# Puente_H.net
KiCad netlist of a schematic drawn in Altium Designer
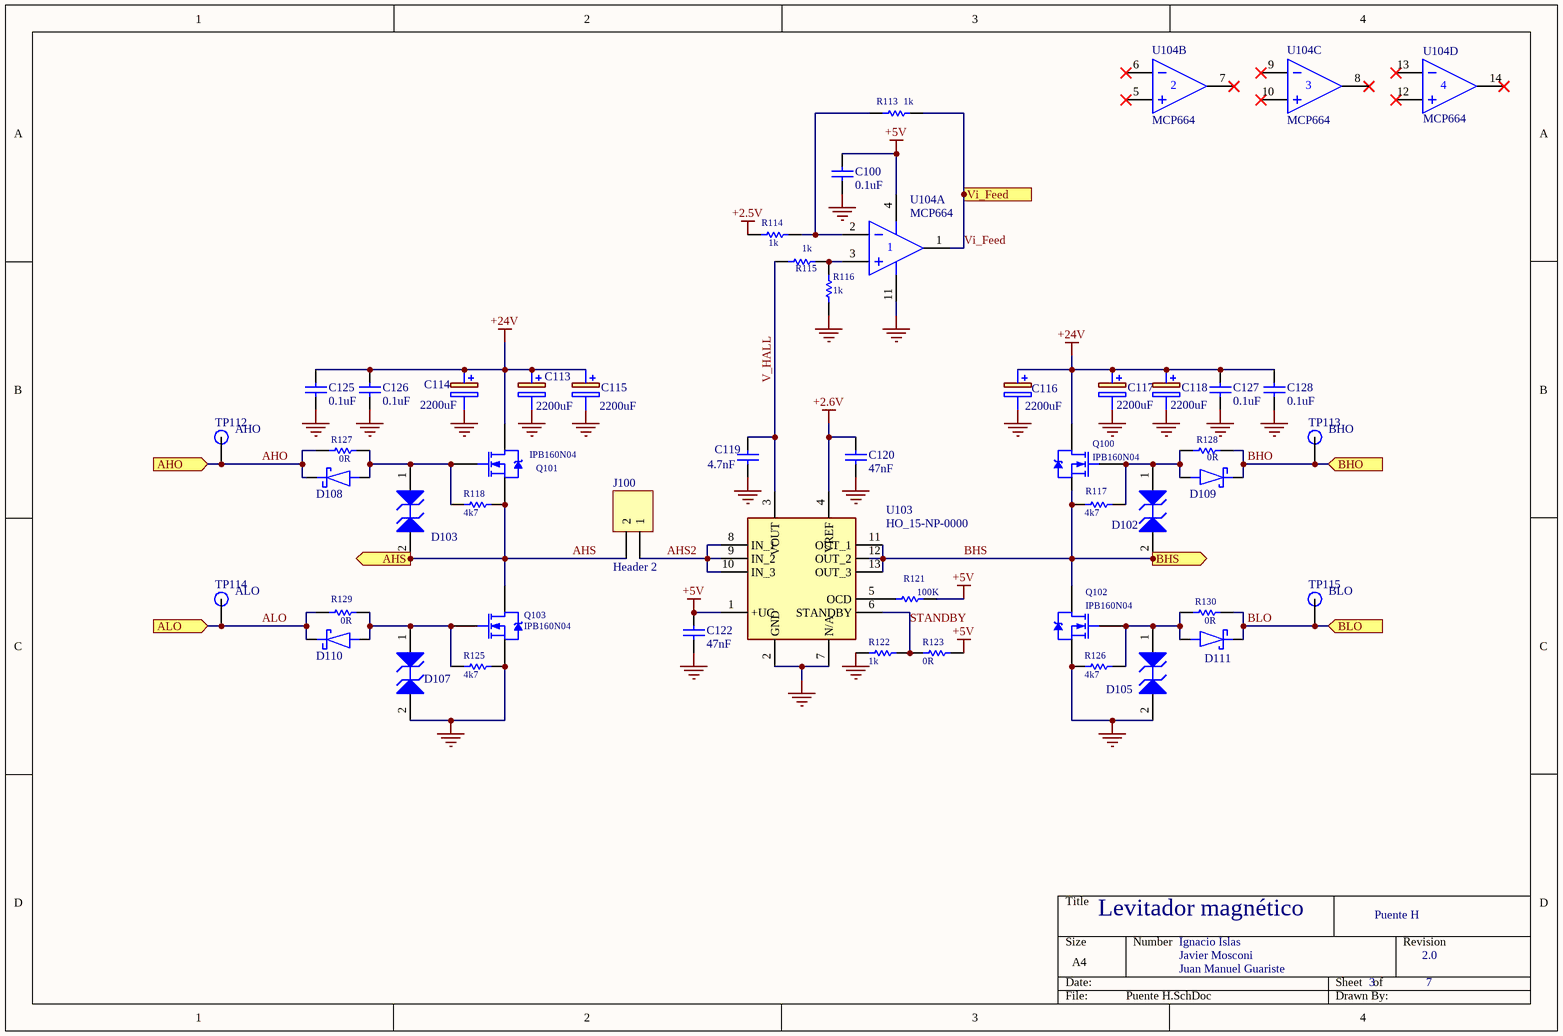
[diagram p0: Puente H.SchDoc]

(export (version "E")
  (design (tool "Eeschema 10.0.6"))
  (components
    (comp (ref "C100")
      (value "0.1uF")
      (footprint "C1206")
      (description "CAP CER 0.1UF 50V X7R 1206")
      (fields (field (name "MANUFACTURER") "Venkel") (field (name "Comment") "Capacitor"))
      (libsource (lib "Levitador_GMI") (part "Capacitor"))
    )
    (comp (ref "C113")
      (value "2200uF")
      (footprint "CAPPRD500W60D1300H2650")
      (description "CAP ALUM 2200UF 20% 35V RADIAL")
      (fields (field (name "MANUFACTURER") "United Chemi-Con") (field (name "Comment") "EKY-350ELL102MK25S"))
      (libsource (lib "Levitador_GMI") (part "EKY-350ELL102MK25S"))
    )
    (comp (ref "C114")
      (value "2200uF")
      (footprint "CAPPRD500W60D1300H2650")
      (description "CAP ALUM 2200UF 20% 35V RADIAL")
      (fields (field (name "MANUFACTURER") "United Chemi-Con") (field (name "Comment") "EKY-350ELL102MK25S"))
      (libsource (lib "Levitador_GMI") (part "EKY-350ELL102MK25S"))
    )
    (comp (ref "C115")
      (value "2200uF")
      (footprint "CAPPRD500W60D1300H2650")
      (description "CAP ALUM 2200UF 20% 35V RADIAL")
      (fields (field (name "MANUFACTURER") "United Chemi-Con") (field (name "Comment") "EKY-350ELL102MK25S"))
      (libsource (lib "Levitador_GMI") (part "EKY-350ELL102MK25S"))
    )
    (comp (ref "C116")
      (value "2200uF")
      (footprint "CAPPRD500W60D1300H2650")
      (description "CAP ALUM 2200UF 20% 35V RADIAL")
      (fields (field (name "MANUFACTURER") "United Chemi-Con") (field (name "Comment") "EKY-350ELL102MK25S"))
      (libsource (lib "Levitador_GMI") (part "EKY-350ELL102MK25S"))
    )
    (comp (ref "C117")
      (value "2200uF")
      (footprint "CAPPRD500W60D1300H2650")
      (description "CAP ALUM 2200UF 20% 35V RADIAL")
      (fields (field (name "MANUFACTURER") "United Chemi-Con") (field (name "Comment") "EKY-350ELL102MK25S"))
      (libsource (lib "Levitador_GMI") (part "EKY-350ELL102MK25S"))
    )
    (comp (ref "C118")
      (value "2200uF")
      (footprint "CAPPRD500W60D1300H2650")
      (description "CAP ALUM 2200UF 20% 35V RADIAL")
      (fields (field (name "MANUFACTURER") "United Chemi-Con") (field (name "Comment") "EKY-350ELL102MK25S"))
      (libsource (lib "Levitador_GMI") (part "EKY-350ELL102MK25S"))
    )
    (comp (ref "C119")
      (value "4.7nF")
      (footprint "C1206")
      (description "CAP CER 4700PF 200V X7R 1206")
      (fields (field (name "MANUFACTURER") "CAL-CHIP ELECTRONICS, INC.") (field (name "Comment") "Capacitor"))
      (libsource (lib "Levitador_GMI") (part "Capacitor"))
    )
    (comp (ref "C120")
      (value "47nF")
      (footprint "C1206")
      (description "CAP CER 0.047UF 50V C0G/NP0 1206")
      (fields (field (name "MANUFACTURER") "CAL-CHIP ELECTRONICS, INC.") (field (name "Comment") "Capacitor"))
      (libsource (lib "Levitador_GMI") (part "Capacitor"))
    )
    (comp (ref "C122")
      (value "47nF")
      (footprint "C1206")
      (description "CAP CER 0.047UF 50V C0G/NP0 1206")
      (fields (field (name "MANUFACTURER") "CAL-CHIP ELECTRONICS, INC.") (field (name "Comment") "Capacitor"))
      (libsource (lib "Levitador_GMI") (part "Capacitor"))
    )
    (comp (ref "C125")
      (value "0.1uF")
      (footprint "C1206")
      (description "CAP CER 0.1UF 50V X7R 1206")
      (fields (field (name "MANUFACTURER") "Venkel") (field (name "Comment") "Capacitor"))
      (libsource (lib "Levitador_GMI") (part "Capacitor"))
    )
    (comp (ref "C126")
      (value "0.1uF")
      (footprint "C1206")
      (description "CAP CER 0.1UF 50V X7R 1206")
      (fields (field (name "MANUFACTURER") "Venkel") (field (name "Comment") "Capacitor"))
      (libsource (lib "Levitador_GMI") (part "Capacitor"))
    )
    (comp (ref "C127")
      (value "0.1uF")
      (footprint "C1206")
      (description "CAP CER 0.1UF 50V X7R 1206")
      (fields (field (name "MANUFACTURER") "Venkel") (field (name "Comment") "Capacitor"))
      (libsource (lib "Levitador_GMI") (part "Capacitor"))
    )
    (comp (ref "C128")
      (value "0.1uF")
      (footprint "C1206")
      (description "CAP CER 0.1UF 50V X7R 1206")
      (fields (field (name "MANUFACTURER") "Venkel") (field (name "Comment") "Capacitor"))
      (libsource (lib "Levitador_GMI") (part "Capacitor"))
    )
    (comp (ref "D102")
      (value "SMAJ15A")
      (footprint "ONSC-SMA-2-403D-02_F_V")
      (description "TVS DIODE 18VWM 29.2VC DO214AC")
      (fields (field (name "MANUFACTURER") "Littelfuse Inc."))
      (libsource (lib "Levitador_GMI") (part "1SMA60CAT3G"))
    )
    (comp (ref "D103")
      (value "SMAJ15A")
      (footprint "ONSC-SMA-2-403D-02_F_V")
      (description "TVS DIODE 18VWM 29.2VC DO214AC")
      (fields (field (name "MANUFACTURER") "Littelfuse Inc."))
      (libsource (lib "Levitador_GMI") (part "1SMA60CAT3G"))
    )
    (comp (ref "D105")
      (value "SMAJ15A")
      (footprint "ONSC-SMA-2-403D-02_F_V")
      (description "TVS DIODE 18VWM 29.2VC DO214AC")
      (fields (field (name "MANUFACTURER") "Littelfuse Inc."))
      (libsource (lib "Levitador_GMI") (part "1SMA60CAT3G"))
    )
    (comp (ref "D107")
      (value "SMAJ15A")
      (footprint "ONSC-SMA-2-403D-02_F_V")
      (description "TVS DIODE 18VWM 29.2VC DO214AC")
      (fields (field (name "MANUFACTURER") "Littelfuse Inc."))
      (libsource (lib "Levitador_GMI") (part "1SMA60CAT3G"))
    )
    (comp (ref "D108")
      (value "RSX205LAM30TR")
      (footprint "SODFL4725X105N")
      (description "DIODE SCHOTTKY 30V 2A PMDTM")
      (fields (field (name "MANUFACTURER") "ROHM Semiconductor"))
      (libsource (lib "Levitador_GMI") (part "RSX205LAM30TR"))
    )
    (comp (ref "D109")
      (value "RSX205LAM30TR")
      (footprint "SODFL4725X105N")
      (description "DIODE SCHOTTKY 30V 2A PMDTM")
      (fields (field (name "MANUFACTURER") "ROHM Semiconductor"))
      (libsource (lib "Levitador_GMI") (part "RSX205LAM30TR"))
    )
    (comp (ref "D110")
      (value "RSX205LAM30TR")
      (footprint "SODFL4725X105N")
      (description "DIODE SCHOTTKY 30V 2A PMDTM")
      (fields (field (name "MANUFACTURER") "ROHM Semiconductor"))
      (libsource (lib "Levitador_GMI") (part "RSX205LAM30TR"))
    )
    (comp (ref "D111")
      (value "RSX205LAM30TR")
      (footprint "SODFL4725X105N")
      (description "DIODE SCHOTTKY 30V 2A PMDTM")
      (fields (field (name "MANUFACTURER") "ROHM Semiconductor"))
      (libsource (lib "Levitador_GMI") (part "RSX205LAM30TR"))
    )
    (comp (ref "J100")
      (value "Header 2")
      (footprint "SMKDS5-2-9.5")
      (description "TERM BLK 2P SIDE ENT 2.54MM PCB")
      (fields (field (name "MANUFACTURER") "TE Connectivity AMP Connectors"))
      (libsource (lib "Levitador_GMI") (part "Header 2"))
    )
    (comp (ref "Q100")
      (value "IPB160N04")
      (footprint "TO263-7S")
      (description "MOSFET N-CH 40V 160A TO263-7")
      (fields (field (name "MANUFACTURER") "Infineon Technologies"))
      (libsource (lib "Levitador_GMI") (part "IPB160N04"))
    )
    (comp (ref "Q101")
      (value "IPB160N04")
      (footprint "TO263-7S")
      (description "MOSFET N-CH 40V 160A TO263-7")
      (fields (field (name "MANUFACTURER") "Infineon Technologies"))
      (libsource (lib "Levitador_GMI") (part "IPB160N04"))
    )
    (comp (ref "Q102")
      (value "IPB160N04")
      (footprint "TO263-7S")
      (description "MOSFET N-CH 40V 160A TO263-7")
      (fields (field (name "MANUFACTURER") "Infineon Technologies"))
      (libsource (lib "Levitador_GMI") (part "IPB160N04"))
    )
    (comp (ref "Q103")
      (value "IPB160N04")
      (footprint "TO263-7S")
      (description "MOSFET N-CH 40V 160A TO263-7")
      (fields (field (name "MANUFACTURER") "Infineon Technologies"))
      (libsource (lib "Levitador_GMI") (part "IPB160N04"))
    )
    (comp (ref "R113")
      (value "1k")
      (footprint "Levitador_GMI:R1206")
      (description "RES 1K OHM 1% 1/4W 1206")
      (fields (field (name "MANUFACTURER") "Stackpole Electronics Inc") (field (name "TOLERANCE") "1%"))
      (libsource (lib "Levitador_GMI") (part "R1206"))
    )
    (comp (ref "R114")
      (value "1k")
      (footprint "Levitador_GMI:R1206")
      (description "RES 1K OHM 1% 1/4W 1206")
      (fields (field (name "MANUFACTURER") "Stackpole Electronics Inc") (field (name "TOLERANCE") "1%"))
      (libsource (lib "Levitador_GMI") (part "R1206"))
    )
    (comp (ref "R115")
      (value "1k")
      (footprint "Levitador_GMI:R1206")
      (description "RES 1K OHM 1% 1/4W 1206")
      (fields (field (name "MANUFACTURER") "Stackpole Electronics Inc") (field (name "TOLERANCE") "1%"))
      (libsource (lib "Levitador_GMI") (part "R1206"))
    )
    (comp (ref "R116")
      (value "1k")
      (footprint "Levitador_GMI:R1206")
      (description "RES 1K OHM 1% 1/4W 1206")
      (fields (field (name "MANUFACTURER") "Stackpole Electronics Inc") (field (name "TOLERANCE") "1%"))
      (libsource (lib "Levitador_GMI") (part "R1206"))
    )
    (comp (ref "R117")
      (value "4k7")
      (footprint "Levitador_GMI:R1206")
      (description "RES 4.7K OHM 1% 1/4W 1206")
      (fields (field (name "MANUFACTURER") "Stackpole Electronics Inc") (field (name "TOLERANCE") "1%"))
      (libsource (lib "Levitador_GMI") (part "R1206"))
    )
    (comp (ref "R118")
      (value "4k7")
      (footprint "Levitador_GMI:R1206")
      (description "RES 4.7K OHM 1% 1/4W 1206")
      (fields (field (name "MANUFACTURER") "Stackpole Electronics Inc") (field (name "TOLERANCE") "1%"))
      (libsource (lib "Levitador_GMI") (part "R1206"))
    )
    (comp (ref "R121")
      (value "100K")
      (footprint "Levitador_GMI:R1206")
      (description "RES 100K OHM 1% 1/4W 1206")
      (fields (field (name "MANUFACTURER") "Stackpole Electronics Inc") (field (name "TOLERANCE") "1%"))
      (libsource (lib "Levitador_GMI") (part "R1206"))
    )
    (comp (ref "R122")
      (value "1k")
      (footprint "Levitador_GMI:R1206")
      (description "RES 1K OHM 1% 1/4W 1206")
      (fields (field (name "MANUFACTURER") "Stackpole Electronics Inc") (field (name "TOLERANCE") "1%"))
      (libsource (lib "Levitador_GMI") (part "R1206"))
    )
    (comp (ref "R123")
      (value "0R")
      (footprint "Levitador_GMI:R1206")
      (description "RES 0 OHM JUMPER 1/4W 1206")
      (fields (field (name "MANUFACTURER") "Stackpole Electronics Inc"))
      (libsource (lib "Levitador_GMI") (part "R1206"))
    )
    (comp (ref "R125")
      (value "4k7")
      (footprint "Levitador_GMI:R1206")
      (description "RES 4.7K OHM 1% 1/4W 1206")
      (fields (field (name "MANUFACTURER") "Stackpole Electronics Inc") (field (name "TOLERANCE") "1%"))
      (libsource (lib "Levitador_GMI") (part "R1206"))
    )
    (comp (ref "R126")
      (value "4k7")
      (footprint "Levitador_GMI:R1206")
      (description "RES 4.7K OHM 1% 1/4W 1206")
      (fields (field (name "MANUFACTURER") "Stackpole Electronics Inc") (field (name "TOLERANCE") "1%"))
      (libsource (lib "Levitador_GMI") (part "R1206"))
    )
    (comp (ref "R127")
      (value "0R")
      (footprint "Levitador_GMI:R1206")
      (description "RES 0 OHM JUMPER 1/4W 1206")
      (fields (field (name "MANUFACTURER") "Stackpole Electronics Inc"))
      (libsource (lib "Levitador_GMI") (part "R1206"))
    )
    (comp (ref "R128")
      (value "0R")
      (footprint "Levitador_GMI:R1206")
      (description "RES 0 OHM JUMPER 1/4W 1206")
      (fields (field (name "MANUFACTURER") "Stackpole Electronics Inc"))
      (libsource (lib "Levitador_GMI") (part "R1206"))
    )
    (comp (ref "R129")
      (value "0R")
      (footprint "Levitador_GMI:R1206")
      (description "RES 0 OHM JUMPER 1/4W 1206")
      (fields (field (name "MANUFACTURER") "Stackpole Electronics Inc"))
      (libsource (lib "Levitador_GMI") (part "R1206"))
    )
    (comp (ref "R130")
      (value "0R")
      (footprint "Levitador_GMI:R1206")
      (description "RES 0 OHM JUMPER 1/4W 1206")
      (fields (field (name "MANUFACTURER") "Stackpole Electronics Inc"))
      (libsource (lib "Levitador_GMI") (part "R1206"))
    )
    (comp (ref "TP112")
      (value "AHO")
      (footprint "TestPoint Keystone 5000 Silver-Red")
      (description "PC TEST POINT MINIATURE RED")
      (fields (field (name "MANUFACTURER") "Keystone Electronics"))
      (libsource (lib "Levitador_GMI") (part "Testpoint"))
    )
    (comp (ref "TP113")
      (value "BHO")
      (footprint "TestPoint Keystone 5000 Silver-Red")
      (description "PC TEST POINT MINIATURE RED")
      (fields (field (name "MANUFACTURER") "Keystone Electronics"))
      (libsource (lib "Levitador_GMI") (part "Testpoint"))
    )
    (comp (ref "TP114")
      (value "ALO")
      (footprint "TestPoint Keystone 5000 Silver-Red")
      (description "PC TEST POINT MINIATURE RED")
      (fields (field (name "MANUFACTURER") "Keystone Electronics"))
      (libsource (lib "Levitador_GMI") (part "Testpoint"))
    )
    (comp (ref "TP115")
      (value "BLO")
      (footprint "TestPoint Keystone 5000 Silver-Red")
      (description "PC TEST POINT MINIATURE RED")
      (fields (field (name "MANUFACTURER") "Keystone Electronics"))
      (libsource (lib "Levitador_GMI") (part "Testpoint"))
    )
    (comp (ref "U103")
      (value "HO_15-NP-0000")
      (footprint "HO15NP0000")
      (description "SENSOR CURRENT HALL 15A AC/DC")
      (fields (field (name "MANUFACTURER") "LEM USA Inc."))
      (libsource (lib "Levitador_GMI") (part "HO_15-NP-0000"))
    )
    (comp (ref "U104")
      (value "MCP664")
      (footprint "SOIC14")
      (description "IC OPAMP GP 4 CIRCUIT 14TSSOP")
      (fields (field (name "PART NUMBER") "MCP664-E/ST") (field (name "MANUFACTURER") "Microchip Technology"))
      (libsource (lib "Levitador_GMI") (part "MCP664"))
    )
  )
  (nets
    (net (code "1") (name "+2.5V") (class "Default")
      (node (ref "R114") (pin "1") (pinfunction "1_1") (pintype "passive"))
    )
    (net (code "2") (name "+2.6V") (class "Default")
      (node (ref "C120") (pin "1") (pinfunction "1_1") (pintype "passive"))
      (node (ref "U103") (pin "4") (pinfunction "VREF_4") (pintype "passive"))
    )
    (net (code "3") (name "+5V") (class "Default")
      (node (ref "C100") (pin "1") (pinfunction "1_1") (pintype "passive"))
      (node (ref "C122") (pin "2") (pinfunction "2_2") (pintype "passive"))
      (node (ref "R121") (pin "2") (pinfunction "2_2") (pintype "passive"))
      (node (ref "R123") (pin "1") (pinfunction "1_1") (pintype "passive"))
      (node (ref "U103") (pin "1") (pinfunction "+UC_1") (pintype "passive"))
      (node (ref "U104") (pin "4") (pinfunction "V+_4") (pintype "power_in"))
    )
    (net (code "4") (name "+24V") (class "Default")
      (node (ref "C113") (pin "1") (pinfunction "+_1") (pintype "passive"))
      (node (ref "C114") (pin "1") (pinfunction "+_1") (pintype "passive"))
      (node (ref "C115") (pin "1") (pinfunction "+_1") (pintype "passive"))
      (node (ref "C116") (pin "1") (pinfunction "+_1") (pintype "passive"))
      (node (ref "C117") (pin "1") (pinfunction "+_1") (pintype "passive"))
      (node (ref "C118") (pin "1") (pinfunction "+_1") (pintype "passive"))
      (node (ref "C125") (pin "2") (pinfunction "2_2") (pintype "passive"))
      (node (ref "C126") (pin "2") (pinfunction "2_2") (pintype "passive"))
      (node (ref "C127") (pin "2") (pinfunction "2_2") (pintype "passive"))
      (node (ref "C128") (pin "2") (pinfunction "2_2") (pintype "passive"))
      (node (ref "Q100") (pin "4") (pinfunction "D_4") (pintype "passive"))
      (node (ref "Q101") (pin "4") (pinfunction "D_4") (pintype "passive"))
    )
    (net (code "5") (name "/AHO") (class "Default")
      (node (ref "D108") (pin "1") (pinfunction "K_1") (pintype "passive"))
      (node (ref "R127") (pin "1") (pinfunction "1_1") (pintype "passive"))
      (node (ref "TP112") (pin "1") (pinfunction "1_1") (pintype "passive"))
    )
    (net (code "6") (name "/AHS") (class "Default")
      (node (ref "D103") (pin "2") (pinfunction "A2_2") (pintype "passive"))
      (node (ref "J100") (pin "2") (pinfunction "2_2") (pintype "passive"))
      (node (ref "Q101") (pin "2") (pinfunction "S_2") (pintype "passive"))
      (node (ref "Q101") (pin "3") (pinfunction "S_3") (pintype "passive"))
      (node (ref "Q101") (pin "5") (pinfunction "S_5") (pintype "passive"))
      (node (ref "Q101") (pin "6") (pinfunction "S_6") (pintype "passive"))
      (node (ref "Q101") (pin "7") (pinfunction "S_7") (pintype "passive"))
      (node (ref "Q103") (pin "4") (pinfunction "D_4") (pintype "passive"))
      (node (ref "R118") (pin "2") (pinfunction "2_2") (pintype "passive"))
    )
    (net (code "7") (name "/AHS2") (class "Default")
      (node (ref "J100") (pin "1") (pinfunction "1_1") (pintype "passive"))
      (node (ref "U103") (pin "10") (pinfunction "IN_3_10") (pintype "passive"))
      (node (ref "U103") (pin "8") (pinfunction "IN_1_8") (pintype "passive"))
      (node (ref "U103") (pin "9") (pinfunction "IN_2_9") (pintype "passive"))
    )
    (net (code "8") (name "/ALO") (class "Default")
      (node (ref "D110") (pin "1") (pinfunction "K_1") (pintype "passive"))
      (node (ref "R129") (pin "1") (pinfunction "1_1") (pintype "passive"))
      (node (ref "TP114") (pin "1") (pinfunction "1_1") (pintype "passive"))
    )
    (net (code "9") (name "/BHO") (class "Default")
      (node (ref "D109") (pin "1") (pinfunction "K_1") (pintype "passive"))
      (node (ref "R128") (pin "2") (pinfunction "2_2") (pintype "passive"))
      (node (ref "TP113") (pin "1") (pinfunction "1_1") (pintype "passive"))
    )
    (net (code "10") (name "/BHS") (class "Default")
      (node (ref "D102") (pin "2") (pinfunction "A2_2") (pintype "passive"))
      (node (ref "Q100") (pin "2") (pinfunction "S_2") (pintype "passive"))
      (node (ref "Q100") (pin "3") (pinfunction "S_3") (pintype "passive"))
      (node (ref "Q100") (pin "5") (pinfunction "S_5") (pintype "passive"))
      (node (ref "Q100") (pin "6") (pinfunction "S_6") (pintype "passive"))
      (node (ref "Q100") (pin "7") (pinfunction "S_7") (pintype "passive"))
      (node (ref "Q102") (pin "4") (pinfunction "D_4") (pintype "passive"))
      (node (ref "R117") (pin "1") (pinfunction "1_1") (pintype "passive"))
      (node (ref "U103") (pin "11") (pinfunction "OUT_1_11") (pintype "passive"))
      (node (ref "U103") (pin "12") (pinfunction "OUT_2_12") (pintype "passive"))
      (node (ref "U103") (pin "13") (pinfunction "OUT_3_13") (pintype "passive"))
    )
    (net (code "11") (name "/BLO") (class "Default")
      (node (ref "D111") (pin "1") (pinfunction "K_1") (pintype "passive"))
      (node (ref "R130") (pin "2") (pinfunction "2_2") (pintype "passive"))
      (node (ref "TP115") (pin "1") (pinfunction "1_1") (pintype "passive"))
    )
    (net (code "12") (name "/STANDBY") (class "Default")
      (node (ref "R122") (pin "1") (pinfunction "1_1") (pintype "passive"))
      (node (ref "R123") (pin "2") (pinfunction "2_2") (pintype "passive"))
      (node (ref "U103") (pin "6") (pinfunction "STANDBY_6") (pintype "passive"))
    )
    (net (code "13") (name "/V_HALL") (class "Default")
      (node (ref "C119") (pin "2") (pinfunction "2_2") (pintype "passive"))
      (node (ref "R115") (pin "1") (pinfunction "1_1") (pintype "passive"))
      (node (ref "U103") (pin "3") (pinfunction "VOUT_3") (pintype "passive"))
    )
    (net (code "14") (name "/Vi_Feed") (class "Default")
      (node (ref "R113") (pin "2") (pinfunction "2_2") (pintype "passive"))
      (node (ref "U104") (pin "1") (pinfunction "OUT_1") (pintype "passive"))
    )
    (net (code "15") (name "GND") (class "Default")
      (node (ref "C100") (pin "2") (pinfunction "2_2") (pintype "passive"))
      (node (ref "C113") (pin "2") (pinfunction "-_2") (pintype "passive"))
      (node (ref "C114") (pin "2") (pinfunction "-_2") (pintype "passive"))
      (node (ref "C115") (pin "2") (pinfunction "-_2") (pintype "passive"))
      (node (ref "C116") (pin "2") (pinfunction "-_2") (pintype "passive"))
      (node (ref "C117") (pin "2") (pinfunction "-_2") (pintype "passive"))
      (node (ref "C118") (pin "2") (pinfunction "-_2") (pintype "passive"))
      (node (ref "C119") (pin "1") (pinfunction "1_1") (pintype "passive"))
      (node (ref "C120") (pin "2") (pinfunction "2_2") (pintype "passive"))
      (node (ref "C122") (pin "1") (pinfunction "1_1") (pintype "passive"))
      (node (ref "C125") (pin "1") (pinfunction "1_1") (pintype "passive"))
      (node (ref "C126") (pin "1") (pinfunction "1_1") (pintype "passive"))
      (node (ref "C127") (pin "1") (pinfunction "1_1") (pintype "passive"))
      (node (ref "C128") (pin "1") (pinfunction "1_1") (pintype "passive"))
      (node (ref "D105") (pin "2") (pinfunction "A2_2") (pintype "passive"))
      (node (ref "D107") (pin "2") (pinfunction "A2_2") (pintype "passive"))
      (node (ref "Q102") (pin "2") (pinfunction "S_2") (pintype "passive"))
      (node (ref "Q102") (pin "3") (pinfunction "S_3") (pintype "passive"))
      (node (ref "Q102") (pin "5") (pinfunction "S_5") (pintype "passive"))
      (node (ref "Q102") (pin "6") (pinfunction "S_6") (pintype "passive"))
      (node (ref "Q102") (pin "7") (pinfunction "S_7") (pintype "passive"))
      (node (ref "Q103") (pin "2") (pinfunction "S_2") (pintype "passive"))
      (node (ref "Q103") (pin "3") (pinfunction "S_3") (pintype "passive"))
      (node (ref "Q103") (pin "5") (pinfunction "S_5") (pintype "passive"))
      (node (ref "Q103") (pin "6") (pinfunction "S_6") (pintype "passive"))
      (node (ref "Q103") (pin "7") (pinfunction "S_7") (pintype "passive"))
      (node (ref "R116") (pin "1") (pinfunction "1_1") (pintype "passive"))
      (node (ref "R122") (pin "2") (pinfunction "2_2") (pintype "passive"))
      (node (ref "R125") (pin "2") (pinfunction "2_2") (pintype "passive"))
      (node (ref "R126") (pin "1") (pinfunction "1_1") (pintype "passive"))
      (node (ref "U103") (pin "2") (pinfunction "GND_2") (pintype "passive"))
      (node (ref "U103") (pin "7") (pinfunction "N/A_7") (pintype "passive"))
      (node (ref "U104") (pin "11") (pinfunction "V-_11") (pintype "power_in"))
    )
    (net (code "16") (name "Net-(D102-A1)") (class "Default")
      (node (ref "D102") (pin "1") (pinfunction "A1_1") (pintype "passive"))
      (node (ref "D109") (pin "2") (pinfunction "A_2") (pintype "passive"))
      (node (ref "Q100") (pin "1") (pinfunction "G_1") (pintype "passive"))
      (node (ref "R117") (pin "2") (pinfunction "2_2") (pintype "passive"))
      (node (ref "R128") (pin "1") (pinfunction "1_1") (pintype "passive"))
    )
    (net (code "17") (name "Net-(D103-A1)") (class "Default")
      (node (ref "D103") (pin "1") (pinfunction "A1_1") (pintype "passive"))
      (node (ref "D108") (pin "2") (pinfunction "A_2") (pintype "passive"))
      (node (ref "Q101") (pin "1") (pinfunction "G_1") (pintype "passive"))
      (node (ref "R118") (pin "1") (pinfunction "1_1") (pintype "passive"))
      (node (ref "R127") (pin "2") (pinfunction "2_2") (pintype "passive"))
    )
    (net (code "18") (name "Net-(D105-A1)") (class "Default")
      (node (ref "D105") (pin "1") (pinfunction "A1_1") (pintype "passive"))
      (node (ref "D111") (pin "2") (pinfunction "A_2") (pintype "passive"))
      (node (ref "Q102") (pin "1") (pinfunction "G_1") (pintype "passive"))
      (node (ref "R126") (pin "2") (pinfunction "2_2") (pintype "passive"))
      (node (ref "R130") (pin "1") (pinfunction "1_1") (pintype "passive"))
    )
    (net (code "19") (name "Net-(D107-A1)") (class "Default")
      (node (ref "D107") (pin "1") (pinfunction "A1_1") (pintype "passive"))
      (node (ref "D110") (pin "2") (pinfunction "A_2") (pintype "passive"))
      (node (ref "Q103") (pin "1") (pinfunction "G_1") (pintype "passive"))
      (node (ref "R125") (pin "1") (pinfunction "1_1") (pintype "passive"))
      (node (ref "R129") (pin "2") (pinfunction "2_2") (pintype "passive"))
    )
    (net (code "20") (name "Net-(U103-OCD)") (class "Default")
      (node (ref "R121") (pin "1") (pinfunction "1_1") (pintype "passive"))
      (node (ref "U103") (pin "5") (pinfunction "OCD_5") (pintype "passive"))
    )
    (net (code "21") (name "Net-(U104A-IN+)") (class "Default")
      (node (ref "R115") (pin "2") (pinfunction "2_2") (pintype "passive"))
      (node (ref "R116") (pin "2") (pinfunction "2_2") (pintype "passive"))
      (node (ref "U104") (pin "3") (pinfunction "IN+_3") (pintype "passive"))
    )
    (net (code "22") (name "Net-(U104A-IN-)") (class "Default")
      (node (ref "R113") (pin "1") (pinfunction "1_1") (pintype "passive"))
      (node (ref "R114") (pin "2") (pinfunction "2_2") (pintype "passive"))
      (node (ref "U104") (pin "2") (pinfunction "IN-_2") (pintype "passive"))
    )
    (net (code "23") (name "unconnected-(U104B-IN+-Pad5)") (class "Default")
      (node (ref "U104") (pin "5") (pinfunction "IN+_5") (pintype "passive+no_connect"))
    )
    (net (code "24") (name "unconnected-(U104B-IN--Pad6)") (class "Default")
      (node (ref "U104") (pin "6") (pinfunction "IN-_6") (pintype "passive+no_connect"))
    )
    (net (code "25") (name "unconnected-(U104B-OUT-Pad7)") (class "Default")
      (node (ref "U104") (pin "7") (pinfunction "OUT_7") (pintype "passive+no_connect"))
    )
    (net (code "26") (name "unconnected-(U104C-IN+-Pad10)") (class "Default")
      (node (ref "U104") (pin "10") (pinfunction "IN+_10") (pintype "passive+no_connect"))
    )
    (net (code "27") (name "unconnected-(U104C-IN--Pad9)") (class "Default")
      (node (ref "U104") (pin "9") (pinfunction "IN-_9") (pintype "passive+no_connect"))
    )
    (net (code "28") (name "unconnected-(U104C-OUT-Pad8)") (class "Default")
      (node (ref "U104") (pin "8") (pinfunction "OUT_8") (pintype "passive+no_connect"))
    )
    (net (code "29") (name "unconnected-(U104D-IN+-Pad12)") (class "Default")
      (node (ref "U104") (pin "12") (pinfunction "IN+_12") (pintype "passive+no_connect"))
    )
    (net (code "30") (name "unconnected-(U104D-IN--Pad13)") (class "Default")
      (node (ref "U104") (pin "13") (pinfunction "IN-_13") (pintype "passive+no_connect"))
    )
    (net (code "31") (name "unconnected-(U104D-OUT-Pad14)") (class "Default")
      (node (ref "U104") (pin "14") (pinfunction "OUT_14") (pintype "passive+no_connect"))
    )
  )
)
